# Motor-Y.net
KiCad netlist of a schematic drawn in Altium Designer
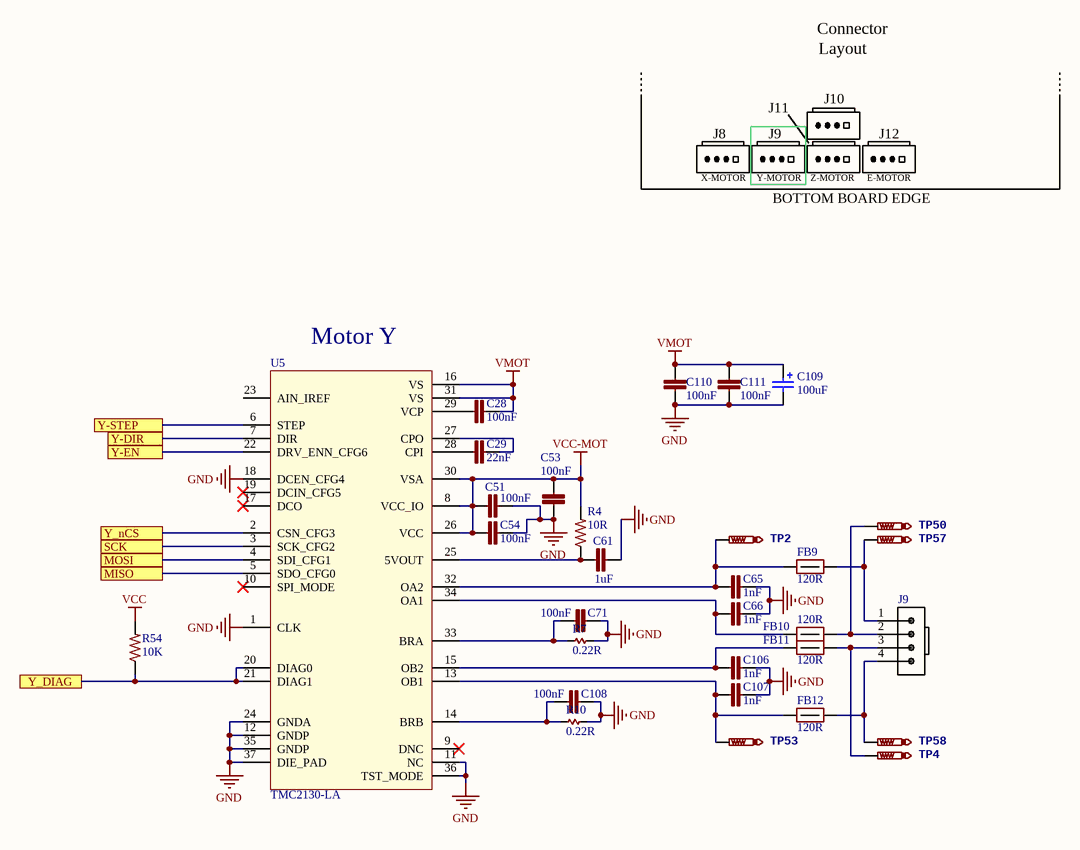
[diagram p0: Motor-Y.SchDoc]

(export (version "E")
  (design (tool "Eeschema 10.0.6"))
  (components
    (comp (ref "C28")
      (value "100nF")
      (footprint "C0603")
      (description "CAP CER 0603 100nF 50V 10% X7R")
      (fields (field (name "MANUFACTURER") "Kemet") (field (name "TOLERANCE") "+/- 10%"))
      (libsource (lib "") (part "C0603C104K5RACTU_2"))
    )
    (comp (ref "C29")
      (value "22nF")
      (footprint "C0402")
      (description "CAP CER 0402 22nF ±10% 50V X7R")
      (fields (field (name "MANUFACTURER") "YAGEO") (field (name "TOLERANCE") "+/- 10%"))
      (libsource (lib "3Delight") (part "GCM155R71H223KA55D"))
    )
    (comp (ref "C51")
      (value "100nF")
      (footprint "C0402")
      (description "CAP CER 0402 100nF 16V 10% X7R")
      (fields (field (name "MANUFACTURER") "Murata") (field (name "TOLERANCE") "+/- 10%"))
      (libsource (lib "") (part "GRM155R71C104KA88D_1"))
    )
    (comp (ref "C53")
      (value "100nF")
      (footprint "C0402")
      (description "CAP CER 0402 100nF 16V 10% X7R")
      (fields (field (name "MANUFACTURER") "Murata") (field (name "TOLERANCE") "+/- 10%"))
      (libsource (lib "3Delight") (part "GRM155R71C104KA88D"))
    )
    (comp (ref "C54")
      (value "100nF")
      (footprint "C0402")
      (description "CAP CER 0402 100nF 16V 10% X7R")
      (fields (field (name "MANUFACTURER") "Murata") (field (name "TOLERANCE") "+/- 10%"))
      (libsource (lib "") (part "GRM155R71C104KA88D_1"))
    )
    (comp (ref "C61")
      (value "1uF")
      (footprint "C0402")
      (description "CAP CER 0402 1uF 6.3V 10% X5R")
      (fields (field (name "MANUFACTURER") "Murata") (field (name "TOLERANCE") "+/- 10%"))
      (libsource (lib "3Delight") (part "GRM155R60J105KE19D"))
    )
    (comp (ref "C65")
      (value "1nF")
      (footprint "C0603")
      (description "CAP CER 0603  1nF 50v 10% X7R")
      (fields (field (name "MANUFACTURER") "Kemet") (field (name "TOLERANCE") "+/- 10%"))
      (libsource (lib "3Delight") (part "C0603C102K5RACTU"))
    )
    (comp (ref "C66")
      (value "1nF")
      (footprint "C0603")
      (description "CAP CER 0603  1nF 50v 10% X7R")
      (fields (field (name "MANUFACTURER") "Kemet") (field (name "TOLERANCE") "+/- 10%"))
      (libsource (lib "3Delight") (part "C0603C102K5RACTU"))
    )
    (comp (ref "C71")
      (value "100nF")
      (footprint "C0603")
      (description "CAP CER 0603 100nF 50V 10% X7R")
      (fields (field (name "MANUFACTURER") "Kemet") (field (name "TOLERANCE") "+/- 10%"))
      (libsource (lib "3Delight") (part "C0603C104K5RACTU"))
    )
    (comp (ref "C106")
      (value "1nF")
      (footprint "C0603")
      (description "CAP CER 0603  1nF 50v 10% X7R")
      (fields (field (name "MANUFACTURER") "Kemet") (field (name "TOLERANCE") "+/- 10%"))
      (libsource (lib "3Delight") (part "C0603C102K5RACTU"))
    )
    (comp (ref "C107")
      (value "1nF")
      (footprint "C0603")
      (description "CAP CER 0603  1nF 50v 10% X7R")
      (fields (field (name "MANUFACTURER") "Kemet") (field (name "TOLERANCE") "+/- 10%"))
      (libsource (lib "3Delight") (part "C0603C102K5RACTU"))
    )
    (comp (ref "C108")
      (value "100nF")
      (footprint "C0603")
      (description "CAP CER 0603 100nF 50V 10% X7R")
      (fields (field (name "MANUFACTURER") "Kemet") (field (name "TOLERANCE") "+/- 10%"))
      (libsource (lib "3Delight") (part "C0603C104K5RACTU"))
    )
    (comp (ref "C109")
      (value "100uF")
      (footprint "CAP-ELEC-063063077")
      (description "CAP ALUM 100UF 35V 20% SMD")
      (fields (field (name "MANUFACTURER") "Nichicon") (field (name "TOLERANCE") "+/- 20%"))
      (libsource (lib "3Delight") (part "UWT1V101MCL1GS"))
    )
    (comp (ref "C110")
      (value "100nF")
      (footprint "C0603")
      (description "CAP CER 0603 100nF 50V 10% X7R")
      (fields (field (name "MANUFACTURER") "Kemet") (field (name "TOLERANCE") "+/- 10%"))
      (libsource (lib "") (part "C0603C104K5RACTU_1"))
    )
    (comp (ref "C111")
      (value "100nF")
      (footprint "C0603")
      (description "CAP CER 0603 100nF 50V 10% X7R")
      (fields (field (name "MANUFACTURER") "Kemet") (field (name "TOLERANCE") "+/- 10%"))
      (libsource (lib "") (part "C0603C104K5RACTU_1"))
    )
    (comp (ref "FB9")
      (value "120R")
      (footprint "FB0603")
      (description "FERRITE BEAD 120 OHM 0603 1LN")
      (fields (field (name "MANUFACTURER") "Samsung") (field (name "PART") "FERRITE 120R 3A 0603"))
      (libsource (lib "Inductors") (part "FERRITE 120R 3A 0603"))
    )
    (comp (ref "FB10")
      (value "120R")
      (footprint "FB0603")
      (description "FERRITE BEAD 120 OHM 0603 1LN")
      (fields (field (name "MANUFACTURER") "Samsung") (field (name "PART") "FERRITE 120R 3A 0603"))
      (libsource (lib "Inductors") (part "FERRITE 120R 3A 0603"))
    )
    (comp (ref "FB11")
      (value "120R")
      (footprint "FB0603")
      (description "FERRITE BEAD 120 OHM 0603 1LN")
      (fields (field (name "MANUFACTURER") "Samsung") (field (name "PART") "FERRITE 120R 3A 0603"))
      (libsource (lib "Inductors") (part "FERRITE 120R 3A 0603"))
    )
    (comp (ref "FB12")
      (value "120R")
      (footprint "FB0603")
      (description "FERRITE BEAD 120 OHM 0603 1LN")
      (fields (field (name "MANUFACTURER") "Samsung") (field (name "PART") "FERRITE 120R 3A 0603"))
      (libsource (lib "Inductors") (part "FERRITE 120R 3A 0603"))
    )
    (comp (ref "J9")
      (value "Molex 0705430003")
      (footprint "4POL254 PIN-IN-PASTE")
      (description "Molex 4 Pin Clip Connector")
      (libsource (lib "Connectors") (part "Molex 0705430003 PIN-IN-PASTE"))
    )
    (comp (ref "R4")
      (value "10R")
      (footprint "R0402")
      (description "RES SMD 10 OHM 1% 1/16W 0402")
      (fields (field (name "MANUFACTURER") "Yageo") (field (name "TOLERANCE") "+/- 1%"))
      (libsource (lib "3Delight") (part "RC0402FR-0710RL"))
    )
    (comp (ref "R7")
      (value "0.22R")
      (footprint "R1206")
      (description "RES SMD 0.22 OHM 1% 1/3W 1206")
      (fields (field (name "MANUFACTURER") "Panasonic") (field (name "TOLERANCE") "+/- 1%"))
      (libsource (lib "Resistors") (part "0.22R 1% 1206"))
    )
    (comp (ref "R10")
      (value "0.22R")
      (footprint "R1206")
      (description "RES SMD 0.22 OHM 1% 1/3W 1206")
      (fields (field (name "MANUFACTURER") "Panasonic") (field (name "TOLERANCE") "+/- 1%"))
      (libsource (lib "Resistors") (part "0.22R 1% 1206"))
    )
    (comp (ref "R54")
      (value "10K")
      (footprint "R0402")
      (description "RES SMD 10K OHM 1% 1/16W 0402")
      (fields (field (name "MANUFACTURER") "Yageo") (field (name "PART") "10k 1% 0402"))
      (libsource (lib "3Delight") (part "RC0402FR-0710KP"))
    )
    (comp (ref "TP2")
      (value "TestPoint")
      (footprint "TP1-27")
      (description "Test Point")
      (libsource (lib "3Delight") (part "TestPoint"))
    )
    (comp (ref "TP4")
      (value "TestPoint")
      (footprint "TP1-27")
      (description "Test Point")
      (libsource (lib "3Delight") (part "TestPoint"))
    )
    (comp (ref "TP50")
      (value "TestPoint")
      (footprint "TP1-27")
      (description "Test Point")
      (libsource (lib "3Delight") (part "TestPoint"))
    )
    (comp (ref "TP53")
      (value "TestPoint")
      (footprint "TP1-27")
      (description "Test Point")
      (libsource (lib "3Delight") (part "TestPoint"))
    )
    (comp (ref "TP57")
      (value "TestPoint")
      (footprint "TP1-27")
      (description "Test Point")
      (libsource (lib "3Delight") (part "TestPoint"))
    )
    (comp (ref "TP58")
      (value "TestPoint")
      (footprint "TP1-27")
      (description "Test Point")
      (libsource (lib "3Delight") (part "TestPoint"))
    )
    (comp (ref "U5")
      (value "TMC2130-LA")
      (footprint "QFN36-DualSolderMask")
      (description "IC STEPPER MOTOR DVR SPI 36QFN")
      (fields (field (name "MANUFACTURER") "Trinamic") (field (name "PART") "TMC2130"))
      (libsource (lib "ICs-Motor Controller") (part "TMC2130-DualSolderMask"))
    )
  )
  (nets
    (net (code "1") (name "/MISO") (class "Default")
      (node (ref "U5") (pin "5") (pinfunction "SDO_CFG0_5") (pintype "passive"))
    )
    (net (code "2") (name "/MOSI") (class "Default")
      (node (ref "U5") (pin "4") (pinfunction "SDI_CFG1_4") (pintype "passive"))
    )
    (net (code "3") (name "/SCK") (class "Default")
      (node (ref "U5") (pin "3") (pinfunction "SCK_CFG2_3") (pintype "passive"))
    )
    (net (code "4") (name "/Y-DIR") (class "Default")
      (node (ref "U5") (pin "7") (pinfunction "DIR_7") (pintype "passive"))
    )
    (net (code "5") (name "/Y-EN") (class "Default")
      (node (ref "U5") (pin "22") (pinfunction "DRV_ENN_CFG6_22") (pintype "passive"))
    )
    (net (code "6") (name "/Y-STEP") (class "Default")
      (node (ref "U5") (pin "6") (pinfunction "STEP_6") (pintype "passive"))
    )
    (net (code "7") (name "/Y_DIAG") (class "Default")
      (node (ref "R54") (pin "1") (pinfunction "1_1") (pintype "passive"))
      (node (ref "U5") (pin "20") (pinfunction "DIAG0_20") (pintype "passive"))
      (node (ref "U5") (pin "21") (pinfunction "DIAG1_21") (pintype "passive"))
    )
    (net (code "8") (name "/Y_nCS") (class "Default")
      (node (ref "U5") (pin "2") (pinfunction "CSN_CFG3_2") (pintype "passive"))
    )
    (net (code "9") (name "GND") (class "Default")
      (node (ref "C106") (pin "2") (pinfunction "2_2") (pintype "passive"))
      (node (ref "C107") (pin "2") (pinfunction "2_2") (pintype "passive"))
      (node (ref "C108") (pin "1") (pinfunction "1_1") (pintype "passive"))
      (node (ref "C109") (pin "2") (pinfunction "2_2") (pintype "passive"))
      (node (ref "C110") (pin "1") (pinfunction "1_1") (pintype "passive"))
      (node (ref "C111") (pin "1") (pinfunction "1_1") (pintype "passive"))
      (node (ref "C51") (pin "1") (pinfunction "1_1") (pintype "passive"))
      (node (ref "C53") (pin "1") (pinfunction "1_1") (pintype "passive"))
      (node (ref "C54") (pin "1") (pinfunction "1_1") (pintype "passive"))
      (node (ref "C61") (pin "2") (pinfunction "2_2") (pintype "passive"))
      (node (ref "C65") (pin "2") (pinfunction "2_2") (pintype "passive"))
      (node (ref "C66") (pin "2") (pinfunction "2_2") (pintype "passive"))
      (node (ref "C71") (pin "1") (pinfunction "1_1") (pintype "passive"))
      (node (ref "R10") (pin "2") (pinfunction "2_2") (pintype "passive"))
      (node (ref "R7") (pin "2") (pinfunction "2_2") (pintype "passive"))
      (node (ref "U5") (pin "1") (pinfunction "CLK_1") (pintype "passive"))
      (node (ref "U5") (pin "11") (pinfunction "NC_11") (pintype "passive"))
      (node (ref "U5") (pin "12") (pinfunction "GNDP_12") (pintype "passive"))
      (node (ref "U5") (pin "18") (pinfunction "DCEN_CFG4_18") (pintype "passive"))
      (node (ref "U5") (pin "24") (pinfunction "GNDA_24") (pintype "passive"))
      (node (ref "U5") (pin "35") (pinfunction "GNDP_35") (pintype "passive"))
      (node (ref "U5") (pin "36") (pinfunction "TST_MODE_36") (pintype "passive"))
      (node (ref "U5") (pin "37") (pinfunction "DIE_PAD_37") (pintype "passive"))
    )
    (net (code "10") (name "Net-(FB9-Pad2)") (class "Default")
      (node (ref "FB9") (pin "2") (pinfunction "2_2") (pintype "passive"))
      (node (ref "J9") (pin "1") (pinfunction "1_1") (pintype "passive"))
      (node (ref "TP57") (pin "TP") (pinfunction "TP_TP") (pintype "passive"))
    )
    (net (code "11") (name "Net-(FB10-Pad2)") (class "Default")
      (node (ref "FB10") (pin "2") (pinfunction "2_2") (pintype "passive"))
      (node (ref "J9") (pin "2") (pinfunction "2_2") (pintype "passive"))
      (node (ref "TP50") (pin "TP") (pinfunction "TP_TP") (pintype "passive"))
    )
    (net (code "12") (name "Net-(FB11-Pad2)") (class "Default")
      (node (ref "FB11") (pin "2") (pinfunction "2_2") (pintype "passive"))
      (node (ref "J9") (pin "3") (pinfunction "3_3") (pintype "passive"))
      (node (ref "TP4") (pin "TP") (pinfunction "TP_TP") (pintype "passive"))
    )
    (net (code "13") (name "Net-(FB12-Pad2)") (class "Default")
      (node (ref "FB12") (pin "2") (pinfunction "2_2") (pintype "passive"))
      (node (ref "J9") (pin "4") (pinfunction "4_4") (pintype "passive"))
      (node (ref "TP58") (pin "TP") (pinfunction "TP_TP") (pintype "passive"))
    )
    (net (code "14") (name "Net-(U5-5VOUT)") (class "Default")
      (node (ref "C61") (pin "1") (pinfunction "1_1") (pintype "passive"))
      (node (ref "R4") (pin "1") (pinfunction "1_1") (pintype "passive"))
      (node (ref "U5") (pin "25") (pinfunction "5VOUT_25") (pintype "passive"))
    )
    (net (code "15") (name "Net-(U5-BRA)") (class "Default")
      (node (ref "C71") (pin "2") (pinfunction "2_2") (pintype "passive"))
      (node (ref "R7") (pin "1") (pinfunction "1_1") (pintype "passive"))
      (node (ref "U5") (pin "33") (pinfunction "BRA_33") (pintype "passive"))
    )
    (net (code "16") (name "Net-(U5-BRB)") (class "Default")
      (node (ref "C108") (pin "2") (pinfunction "2_2") (pintype "passive"))
      (node (ref "R10") (pin "1") (pinfunction "1_1") (pintype "passive"))
      (node (ref "U5") (pin "14") (pinfunction "BRB_14") (pintype "passive"))
    )
    (net (code "17") (name "Net-(U5-CPI)") (class "Default")
      (node (ref "C29") (pin "1") (pinfunction "1_1") (pintype "passive"))
      (node (ref "U5") (pin "28") (pinfunction "CPI_28") (pintype "passive"))
    )
    (net (code "18") (name "Net-(U5-CPO)") (class "Default")
      (node (ref "C29") (pin "2") (pinfunction "2_2") (pintype "passive"))
      (node (ref "U5") (pin "27") (pinfunction "CPO_27") (pintype "passive"))
    )
    (net (code "19") (name "Net-(U5-OA1)") (class "Default")
      (node (ref "C66") (pin "1") (pinfunction "1_1") (pintype "passive"))
      (node (ref "FB10") (pin "1") (pinfunction "1_1") (pintype "passive"))
      (node (ref "U5") (pin "34") (pinfunction "OA1_34") (pintype "passive"))
    )
    (net (code "20") (name "Net-(U5-OA2)") (class "Default")
      (node (ref "C65") (pin "1") (pinfunction "1_1") (pintype "passive"))
      (node (ref "FB9") (pin "1") (pinfunction "1_1") (pintype "passive"))
      (node (ref "TP2") (pin "TP") (pinfunction "TP_TP") (pintype "passive"))
      (node (ref "U5") (pin "32") (pinfunction "OA2_32") (pintype "passive"))
    )
    (net (code "21") (name "Net-(U5-OB1)") (class "Default")
      (node (ref "C107") (pin "1") (pinfunction "1_1") (pintype "passive"))
      (node (ref "FB12") (pin "1") (pinfunction "1_1") (pintype "passive"))
      (node (ref "TP53") (pin "TP") (pinfunction "TP_TP") (pintype "passive"))
      (node (ref "U5") (pin "13") (pinfunction "OB1_13") (pintype "passive"))
    )
    (net (code "22") (name "Net-(U5-OB2)") (class "Default")
      (node (ref "C106") (pin "1") (pinfunction "1_1") (pintype "passive"))
      (node (ref "FB11") (pin "1") (pinfunction "1_1") (pintype "passive"))
      (node (ref "U5") (pin "15") (pinfunction "OB2_15") (pintype "passive"))
    )
    (net (code "23") (name "Net-(U5-VCP)") (class "Default")
      (node (ref "C28") (pin "1") (pinfunction "1_1") (pintype "passive"))
      (node (ref "U5") (pin "29") (pinfunction "VCP_29") (pintype "passive"))
    )
    (net (code "24") (name "VCC") (class "Default")
      (node (ref "R54") (pin "2") (pinfunction "2_2") (pintype "passive"))
    )
    (net (code "25") (name "VCC-MOT") (class "Default")
      (node (ref "C51") (pin "2") (pinfunction "2_2") (pintype "passive"))
      (node (ref "C53") (pin "2") (pinfunction "2_2") (pintype "passive"))
      (node (ref "C54") (pin "2") (pinfunction "2_2") (pintype "passive"))
      (node (ref "R4") (pin "2") (pinfunction "2_2") (pintype "passive"))
      (node (ref "U5") (pin "26") (pinfunction "VCC_26") (pintype "passive"))
      (node (ref "U5") (pin "30") (pinfunction "VSA_30") (pintype "passive"))
      (node (ref "U5") (pin "8") (pinfunction "VCC_IO_8") (pintype "passive"))
    )
    (net (code "26") (name "VMOT") (class "Default")
      (node (ref "C109") (pin "1") (pinfunction "1_1") (pintype "passive"))
      (node (ref "C110") (pin "2") (pinfunction "2_2") (pintype "passive"))
      (node (ref "C111") (pin "2") (pinfunction "2_2") (pintype "passive"))
      (node (ref "C28") (pin "2") (pinfunction "2_2") (pintype "passive"))
      (node (ref "U5") (pin "16") (pinfunction "VS_16") (pintype "passive"))
      (node (ref "U5") (pin "31") (pinfunction "VS_31") (pintype "passive"))
    )
    (net (code "27") (name "unconnected-(U5-AIN_IREF-Pad23)") (class "Default")
      (node (ref "U5") (pin "23") (pinfunction "AIN_IREF_23") (pintype "passive"))
    )
    (net (code "28") (name "unconnected-(U5-DCIN_CFG5-Pad19)") (class "Default")
      (node (ref "U5") (pin "19") (pinfunction "DCIN_CFG5_19") (pintype "passive+no_connect"))
    )
    (net (code "29") (name "unconnected-(U5-DCO-Pad17)") (class "Default")
      (node (ref "U5") (pin "17") (pinfunction "DCO_17") (pintype "passive+no_connect"))
    )
    (net (code "30") (name "unconnected-(U5-DNC-Pad9)") (class "Default")
      (node (ref "U5") (pin "9") (pinfunction "DNC_9") (pintype "passive+no_connect"))
    )
    (net (code "31") (name "unconnected-(U5-SPI_MODE-Pad10)") (class "Default")
      (node (ref "U5") (pin "10") (pinfunction "SPI_MODE_10") (pintype "passive+no_connect"))
    )
  )
)
